# SCH_Tap-Touch-ESP32_2025-01-30.net
KiCad netlist of a schematic drawn in EasyEDA
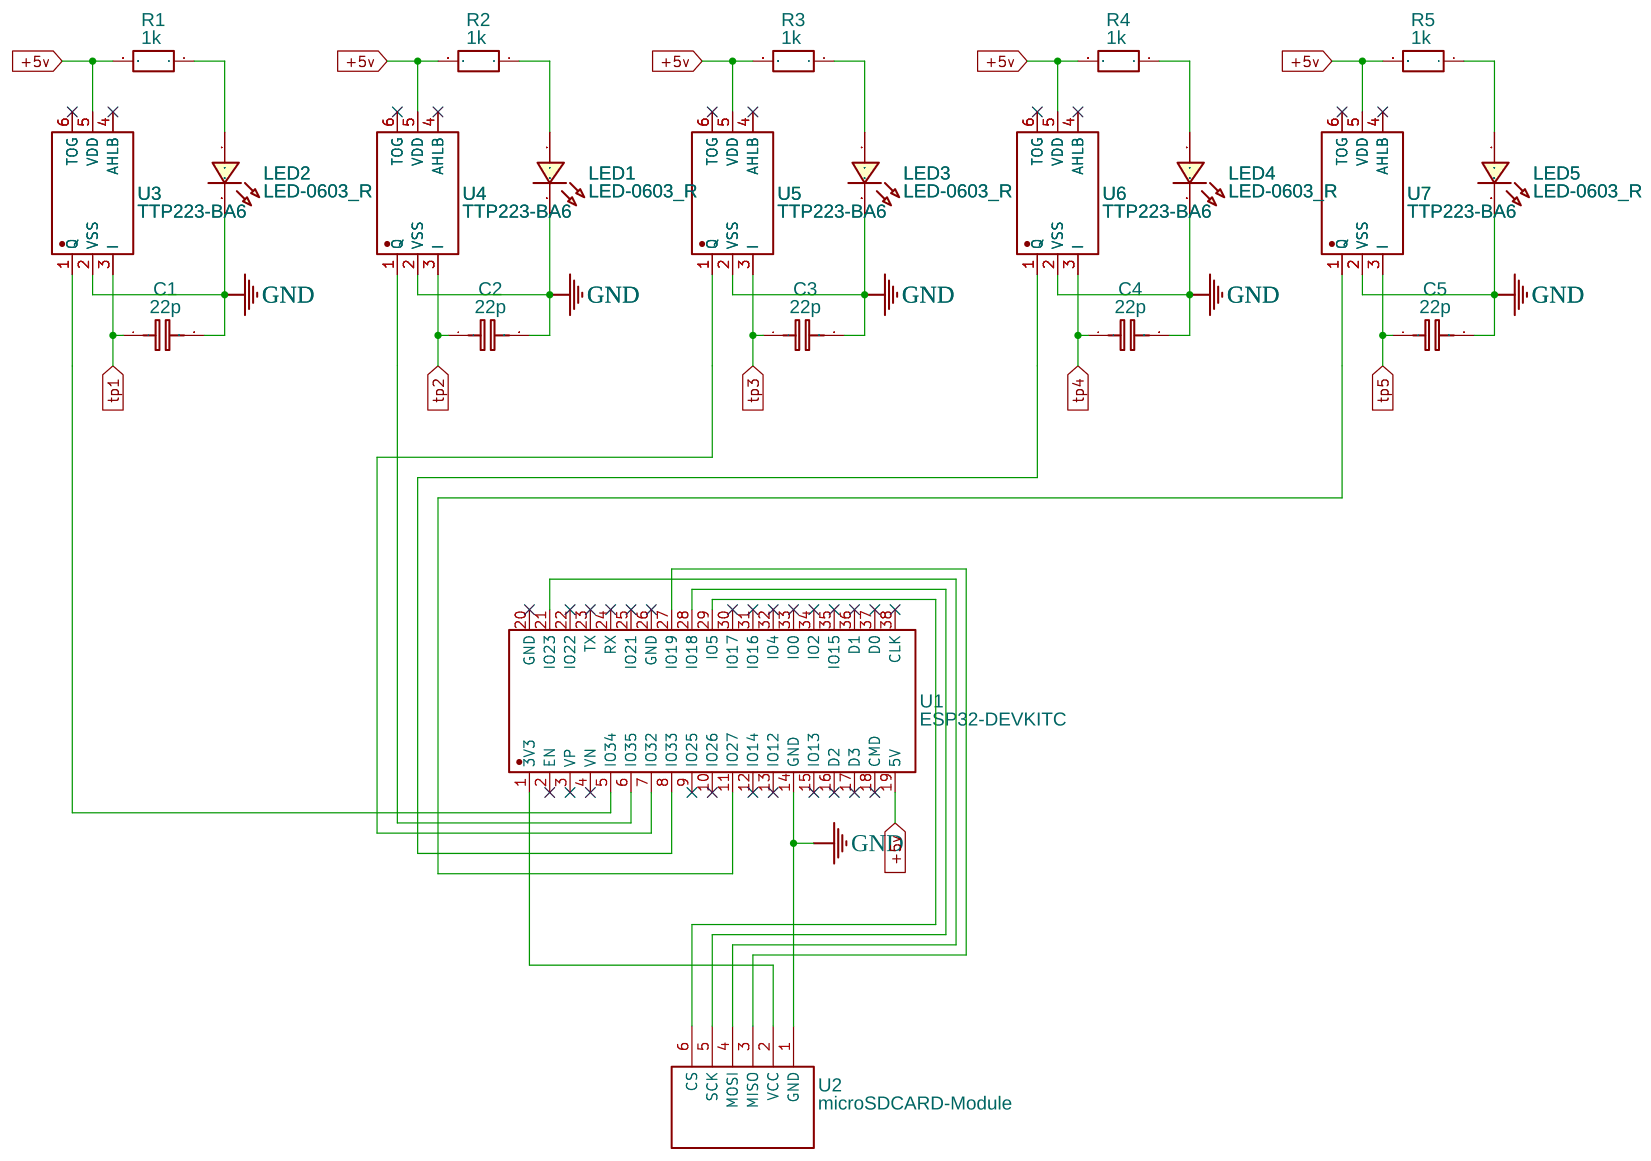
[diagram p0: schematic sheet]

(export (version "E")
  (design (tool "Eeschema 10.0.6"))
  (components
    (comp (ref "C1") (value "22p") (libsource (lib "") (part "C_0603_EU_1")))
    (comp (ref "C2") (value "22p") (libsource (lib "") (part "C_0603_EU_1")))
    (comp (ref "C3") (value "22p") (libsource (lib "") (part "C_0603_EU")))
    (comp (ref "C4") (value "22p") (libsource (lib "") (part "C_0603_EU")))
    (comp (ref "C5") (value "22p") (libsource (lib "") (part "C_0603_EU")))
    (comp (ref "LED1")
      (value "LED-0603_R")
      (fields
        (field (name "Manufacturer Part") "19-217/R6C-AL1M2VY/3T")
        (field (name "Manufacturer") "EVERLIGHT(台湾亿光)")
      )
      (libsource (lib "") (part "LED-0603_R"))
    )
    (comp (ref "LED2")
      (value "LED-0603_R")
      (fields
        (field (name "Manufacturer Part") "19-217/R6C-AL1M2VY/3T")
        (field (name "Manufacturer") "EVERLIGHT(台湾亿光)")
      )
      (libsource (lib "") (part "LED-0603_R"))
    )
    (comp (ref "LED3")
      (value "LED-0603_R")
      (fields
        (field (name "Manufacturer Part") "19-217/R6C-AL1M2VY/3T")
        (field (name "Manufacturer") "EVERLIGHT(台湾亿光)")
      )
      (libsource (lib "") (part "LED-0603_R"))
    )
    (comp (ref "LED4")
      (value "LED-0603_R")
      (fields
        (field (name "Manufacturer Part") "19-217/R6C-AL1M2VY/3T")
        (field (name "Manufacturer") "EVERLIGHT(台湾亿光)")
      )
      (libsource (lib "") (part "LED-0603_R"))
    )
    (comp (ref "LED5")
      (value "LED-0603_R")
      (fields
        (field (name "Manufacturer Part") "19-217/R6C-AL1M2VY/3T")
        (field (name "Manufacturer") "EVERLIGHT(台湾亿光)")
      )
      (libsource (lib "") (part "LED-0603_R"))
    )
    (comp (ref "R1") (value "1k") (libsource (lib "") (part "R_0603_EU")))
    (comp (ref "R2") (value "1k") (libsource (lib "") (part "R_0603_EU")))
    (comp (ref "R3") (value "1k") (libsource (lib "") (part "R_0603_EU")))
    (comp (ref "R4") (value "1k") (libsource (lib "") (part "R_0603_EU")))
    (comp (ref "R5") (value "1k") (libsource (lib "") (part "R_0603_EU")))
    (comp (ref "U1")
      (value "ESP32-DEVKITC")
      (fields
        (field (name "Manufacturer Part") "ESP32-DevKitC")
        (field (name "Manufacturer") "ESPRESSIF(乐鑫)")
      )
      (libsource (lib "") (part "ESP32-DEVKITC"))
    )
    (comp (ref "U2") (value "microSDCARD-Module") (libsource (lib "") (part "microSDCARD-Module")))
    (comp (ref "U3")
      (value "TTP223-BA6")
      (fields (field (name "Manufacturer") "TONTEK(通泰)"))
      (libsource (lib "") (part "TTP223-BA6_C2757936"))
    )
    (comp (ref "U4")
      (value "TTP223-BA6")
      (fields (field (name "Manufacturer") "TONTEK(通泰)"))
      (libsource (lib "") (part "TTP223-BA6_C2757936"))
    )
    (comp (ref "U5")
      (value "TTP223-BA6")
      (fields (field (name "Manufacturer") "TONTEK(通泰)"))
      (libsource (lib "") (part "TTP223-BA6_C2757936"))
    )
    (comp (ref "U6")
      (value "TTP223-BA6")
      (fields (field (name "Manufacturer") "TONTEK(通泰)"))
      (libsource (lib "") (part "TTP223-BA6_C2757936"))
    )
    (comp (ref "U7")
      (value "TTP223-BA6")
      (fields (field (name "Manufacturer") "TONTEK(通泰)"))
      (libsource (lib "") (part "TTP223-BA6_C2757936"))
    )
  )
  (nets
    (net (code "1") (name "+5v") (class "Default")
      (node (ref "R1") (pin "2") (pinfunction "2_2") (pintype "unspecified"))
      (node (ref "R2") (pin "2") (pinfunction "2_2") (pintype "unspecified"))
      (node (ref "R3") (pin "2") (pinfunction "2_2") (pintype "unspecified"))
      (node (ref "R4") (pin "2") (pinfunction "2_2") (pintype "unspecified"))
      (node (ref "R5") (pin "2") (pinfunction "2_2") (pintype "unspecified"))
      (node (ref "U1") (pin "19") (pinfunction "5V_19") (pintype "unspecified"))
      (node (ref "U3") (pin "5") (pinfunction "VDD_5") (pintype "unspecified"))
      (node (ref "U4") (pin "5") (pinfunction "VDD_5") (pintype "unspecified"))
      (node (ref "U5") (pin "5") (pinfunction "VDD_5") (pintype "unspecified"))
      (node (ref "U6") (pin "5") (pinfunction "VDD_5") (pintype "unspecified"))
      (node (ref "U7") (pin "5") (pinfunction "VDD_5") (pintype "unspecified"))
    )
    (net (code "2") (name "GND") (class "Default")
      (node (ref "C1") (pin "2") (pinfunction "2_2") (pintype "unspecified"))
      (node (ref "C2") (pin "2") (pinfunction "2_2") (pintype "unspecified"))
      (node (ref "C3") (pin "2") (pinfunction "2_2") (pintype "unspecified"))
      (node (ref "C4") (pin "2") (pinfunction "2_2") (pintype "unspecified"))
      (node (ref "C5") (pin "2") (pinfunction "2_2") (pintype "unspecified"))
      (node (ref "LED1") (pin "2") (pinfunction "2_2") (pintype "unspecified"))
      (node (ref "LED2") (pin "2") (pinfunction "2_2") (pintype "unspecified"))
      (node (ref "LED3") (pin "2") (pinfunction "2_2") (pintype "unspecified"))
      (node (ref "LED4") (pin "2") (pinfunction "2_2") (pintype "unspecified"))
      (node (ref "LED5") (pin "2") (pinfunction "2_2") (pintype "unspecified"))
      (node (ref "U1") (pin "14") (pinfunction "GND_14") (pintype "unspecified"))
      (node (ref "U2") (pin "1") (pinfunction "GND_1") (pintype "unspecified"))
      (node (ref "U3") (pin "2") (pinfunction "VSS_2") (pintype "unspecified"))
      (node (ref "U4") (pin "2") (pinfunction "VSS_2") (pintype "unspecified"))
      (node (ref "U5") (pin "2") (pinfunction "VSS_2") (pintype "unspecified"))
      (node (ref "U6") (pin "2") (pinfunction "VSS_2") (pintype "unspecified"))
      (node (ref "U7") (pin "2") (pinfunction "VSS_2") (pintype "unspecified"))
    )
    (net (code "3") (name "Net-(LED1-Pad1)") (class "Default")
      (node (ref "LED1") (pin "1") (pinfunction "1_1") (pintype "unspecified"))
      (node (ref "R2") (pin "1") (pinfunction "1_1") (pintype "unspecified"))
    )
    (net (code "4") (name "Net-(LED2-Pad1)") (class "Default")
      (node (ref "LED2") (pin "1") (pinfunction "1_1") (pintype "unspecified"))
      (node (ref "R1") (pin "1") (pinfunction "1_1") (pintype "unspecified"))
    )
    (net (code "5") (name "Net-(LED3-Pad1)") (class "Default")
      (node (ref "LED3") (pin "1") (pinfunction "1_1") (pintype "unspecified"))
      (node (ref "R3") (pin "1") (pinfunction "1_1") (pintype "unspecified"))
    )
    (net (code "6") (name "Net-(LED4-Pad1)") (class "Default")
      (node (ref "LED4") (pin "1") (pinfunction "1_1") (pintype "unspecified"))
      (node (ref "R4") (pin "1") (pinfunction "1_1") (pintype "unspecified"))
    )
    (net (code "7") (name "Net-(LED5-Pad1)") (class "Default")
      (node (ref "LED5") (pin "1") (pinfunction "1_1") (pintype "unspecified"))
      (node (ref "R5") (pin "1") (pinfunction "1_1") (pintype "unspecified"))
    )
    (net (code "8") (name "Net-(U1-3V3)") (class "Default")
      (node (ref "U1") (pin "1") (pinfunction "3V3_1") (pintype "unspecified"))
      (node (ref "U2") (pin "2") (pinfunction "VCC_2") (pintype "unspecified"))
    )
    (net (code "9") (name "Net-(U1-IO5)") (class "Default")
      (node (ref "U1") (pin "29") (pinfunction "IO5_29") (pintype "unspecified"))
      (node (ref "U2") (pin "6") (pinfunction "CS_6") (pintype "unspecified"))
    )
    (net (code "10") (name "Net-(U1-IO18)") (class "Default")
      (node (ref "U1") (pin "28") (pinfunction "IO18_28") (pintype "unspecified"))
      (node (ref "U2") (pin "5") (pinfunction "SCK_5") (pintype "unspecified"))
    )
    (net (code "11") (name "Net-(U1-IO19)") (class "Default")
      (node (ref "U1") (pin "27") (pinfunction "IO19_27") (pintype "unspecified"))
      (node (ref "U2") (pin "3") (pinfunction "MISO_3") (pintype "unspecified"))
    )
    (net (code "12") (name "Net-(U1-IO23)") (class "Default")
      (node (ref "U1") (pin "21") (pinfunction "IO23_21") (pintype "unspecified"))
      (node (ref "U2") (pin "4") (pinfunction "MOSI_4") (pintype "unspecified"))
    )
    (net (code "13") (name "Net-(U1-IO27)") (class "Default")
      (node (ref "U1") (pin "11") (pinfunction "IO27_11") (pintype "unspecified"))
      (node (ref "U7") (pin "1") (pinfunction "Q_1") (pintype "unspecified"))
    )
    (net (code "14") (name "Net-(U1-IO32)") (class "Default")
      (node (ref "U1") (pin "7") (pinfunction "IO32_7") (pintype "unspecified"))
      (node (ref "U5") (pin "1") (pinfunction "Q_1") (pintype "unspecified"))
    )
    (net (code "15") (name "Net-(U1-IO33)") (class "Default")
      (node (ref "U1") (pin "8") (pinfunction "IO33_8") (pintype "unspecified"))
      (node (ref "U6") (pin "1") (pinfunction "Q_1") (pintype "unspecified"))
    )
    (net (code "16") (name "Net-(U1-IO34)") (class "Default")
      (node (ref "U1") (pin "5") (pinfunction "IO34_5") (pintype "unspecified"))
      (node (ref "U3") (pin "1") (pinfunction "Q_1") (pintype "unspecified"))
    )
    (net (code "17") (name "Net-(U1-IO35)") (class "Default")
      (node (ref "U1") (pin "6") (pinfunction "IO35_6") (pintype "unspecified"))
      (node (ref "U4") (pin "1") (pinfunction "Q_1") (pintype "unspecified"))
    )
    (net (code "18") (name "tp1") (class "Default")
      (node (ref "C1") (pin "1") (pinfunction "1_1") (pintype "unspecified"))
      (node (ref "U3") (pin "3") (pinfunction "I_3") (pintype "unspecified"))
    )
    (net (code "19") (name "tp2") (class "Default")
      (node (ref "C2") (pin "1") (pinfunction "1_1") (pintype "unspecified"))
      (node (ref "U4") (pin "3") (pinfunction "I_3") (pintype "unspecified"))
    )
    (net (code "20") (name "tp3") (class "Default")
      (node (ref "C3") (pin "1") (pinfunction "1_1") (pintype "unspecified"))
      (node (ref "U5") (pin "3") (pinfunction "I_3") (pintype "unspecified"))
    )
    (net (code "21") (name "tp4") (class "Default")
      (node (ref "C4") (pin "1") (pinfunction "1_1") (pintype "unspecified"))
      (node (ref "U6") (pin "3") (pinfunction "I_3") (pintype "unspecified"))
    )
    (net (code "22") (name "tp5") (class "Default")
      (node (ref "C5") (pin "1") (pinfunction "1_1") (pintype "unspecified"))
      (node (ref "U7") (pin "3") (pinfunction "I_3") (pintype "unspecified"))
    )
    (net (code "23") (name "unconnected-(U1-CLK-Pad38)") (class "Default")
      (node (ref "U1") (pin "38") (pinfunction "CLK_38") (pintype "unspecified+no_connect"))
    )
    (net (code "24") (name "unconnected-(U1-CMD-Pad18)") (class "Default")
      (node (ref "U1") (pin "18") (pinfunction "CMD_18") (pintype "unspecified+no_connect"))
    )
    (net (code "25") (name "unconnected-(U1-D0-Pad37)") (class "Default")
      (node (ref "U1") (pin "37") (pinfunction "D0_37") (pintype "unspecified+no_connect"))
    )
    (net (code "26") (name "unconnected-(U1-D1-Pad36)") (class "Default")
      (node (ref "U1") (pin "36") (pinfunction "D1_36") (pintype "unspecified+no_connect"))
    )
    (net (code "27") (name "unconnected-(U1-D2-Pad16)") (class "Default")
      (node (ref "U1") (pin "16") (pinfunction "D2_16") (pintype "unspecified+no_connect"))
    )
    (net (code "28") (name "unconnected-(U1-D3-Pad17)") (class "Default")
      (node (ref "U1") (pin "17") (pinfunction "D3_17") (pintype "unspecified+no_connect"))
    )
    (net (code "29") (name "unconnected-(U1-EN-Pad2)") (class "Default")
      (node (ref "U1") (pin "2") (pinfunction "EN_2") (pintype "unspecified+no_connect"))
    )
    (net (code "30") (name "unconnected-(U1-GND-Pad20)") (class "Default")
      (node (ref "U1") (pin "20") (pinfunction "GND_20") (pintype "unspecified+no_connect"))
    )
    (net (code "31") (name "unconnected-(U1-GND-Pad26)") (class "Default")
      (node (ref "U1") (pin "26") (pinfunction "GND_26") (pintype "unspecified+no_connect"))
    )
    (net (code "32") (name "unconnected-(U1-IO0-Pad33)") (class "Default")
      (node (ref "U1") (pin "33") (pinfunction "IO0_33") (pintype "unspecified+no_connect"))
    )
    (net (code "33") (name "unconnected-(U1-IO2-Pad34)") (class "Default")
      (node (ref "U1") (pin "34") (pinfunction "IO2_34") (pintype "unspecified+no_connect"))
    )
    (net (code "34") (name "unconnected-(U1-IO4-Pad32)") (class "Default")
      (node (ref "U1") (pin "32") (pinfunction "IO4_32") (pintype "unspecified+no_connect"))
    )
    (net (code "35") (name "unconnected-(U1-IO12-Pad13)") (class "Default")
      (node (ref "U1") (pin "13") (pinfunction "IO12_13") (pintype "unspecified+no_connect"))
    )
    (net (code "36") (name "unconnected-(U1-IO13-Pad15)") (class "Default")
      (node (ref "U1") (pin "15") (pinfunction "IO13_15") (pintype "unspecified+no_connect"))
    )
    (net (code "37") (name "unconnected-(U1-IO14-Pad12)") (class "Default")
      (node (ref "U1") (pin "12") (pinfunction "IO14_12") (pintype "unspecified+no_connect"))
    )
    (net (code "38") (name "unconnected-(U1-IO15-Pad35)") (class "Default")
      (node (ref "U1") (pin "35") (pinfunction "IO15_35") (pintype "unspecified+no_connect"))
    )
    (net (code "39") (name "unconnected-(U1-IO16-Pad31)") (class "Default")
      (node (ref "U1") (pin "31") (pinfunction "IO16_31") (pintype "unspecified+no_connect"))
    )
    (net (code "40") (name "unconnected-(U1-IO17-Pad30)") (class "Default")
      (node (ref "U1") (pin "30") (pinfunction "IO17_30") (pintype "unspecified+no_connect"))
    )
    (net (code "41") (name "unconnected-(U1-IO21-Pad25)") (class "Default")
      (node (ref "U1") (pin "25") (pinfunction "IO21_25") (pintype "unspecified+no_connect"))
    )
    (net (code "42") (name "unconnected-(U1-IO22-Pad22)") (class "Default")
      (node (ref "U1") (pin "22") (pinfunction "IO22_22") (pintype "unspecified+no_connect"))
    )
    (net (code "43") (name "unconnected-(U1-IO25-Pad9)") (class "Default")
      (node (ref "U1") (pin "9") (pinfunction "IO25_9") (pintype "unspecified+no_connect"))
    )
    (net (code "44") (name "unconnected-(U1-IO26-Pad10)") (class "Default")
      (node (ref "U1") (pin "10") (pinfunction "IO26_10") (pintype "unspecified+no_connect"))
    )
    (net (code "45") (name "unconnected-(U1-RX-Pad24)") (class "Default")
      (node (ref "U1") (pin "24") (pinfunction "RX_24") (pintype "unspecified+no_connect"))
    )
    (net (code "46") (name "unconnected-(U1-TX-Pad23)") (class "Default")
      (node (ref "U1") (pin "23") (pinfunction "TX_23") (pintype "unspecified+no_connect"))
    )
    (net (code "47") (name "unconnected-(U1-VN-Pad4)") (class "Default")
      (node (ref "U1") (pin "4") (pinfunction "VN_4") (pintype "unspecified+no_connect"))
    )
    (net (code "48") (name "unconnected-(U1-VP-Pad3)") (class "Default")
      (node (ref "U1") (pin "3") (pinfunction "VP_3") (pintype "unspecified+no_connect"))
    )
    (net (code "49") (name "unconnected-(U3-AHLB-Pad4)") (class "Default")
      (node (ref "U3") (pin "4") (pinfunction "AHLB_4") (pintype "unspecified+no_connect"))
    )
    (net (code "50") (name "unconnected-(U3-TOG-Pad6)") (class "Default")
      (node (ref "U3") (pin "6") (pinfunction "TOG_6") (pintype "unspecified+no_connect"))
    )
    (net (code "51") (name "unconnected-(U4-AHLB-Pad4)") (class "Default")
      (node (ref "U4") (pin "4") (pinfunction "AHLB_4") (pintype "unspecified+no_connect"))
    )
    (net (code "52") (name "unconnected-(U4-TOG-Pad6)") (class "Default")
      (node (ref "U4") (pin "6") (pinfunction "TOG_6") (pintype "unspecified+no_connect"))
    )
    (net (code "53") (name "unconnected-(U5-AHLB-Pad4)") (class "Default")
      (node (ref "U5") (pin "4") (pinfunction "AHLB_4") (pintype "unspecified+no_connect"))
    )
    (net (code "54") (name "unconnected-(U5-TOG-Pad6)") (class "Default")
      (node (ref "U5") (pin "6") (pinfunction "TOG_6") (pintype "unspecified+no_connect"))
    )
    (net (code "55") (name "unconnected-(U6-AHLB-Pad4)") (class "Default")
      (node (ref "U6") (pin "4") (pinfunction "AHLB_4") (pintype "unspecified+no_connect"))
    )
    (net (code "56") (name "unconnected-(U6-TOG-Pad6)") (class "Default")
      (node (ref "U6") (pin "6") (pinfunction "TOG_6") (pintype "unspecified+no_connect"))
    )
    (net (code "57") (name "unconnected-(U7-AHLB-Pad4)") (class "Default")
      (node (ref "U7") (pin "4") (pinfunction "AHLB_4") (pintype "unspecified+no_connect"))
    )
    (net (code "58") (name "unconnected-(U7-TOG-Pad6)") (class "Default")
      (node (ref "U7") (pin "6") (pinfunction "TOG_6") (pintype "unspecified+no_connect"))
    )
  )
)
